# MCU.net
KiCad netlist of a schematic drawn in Altium Designer
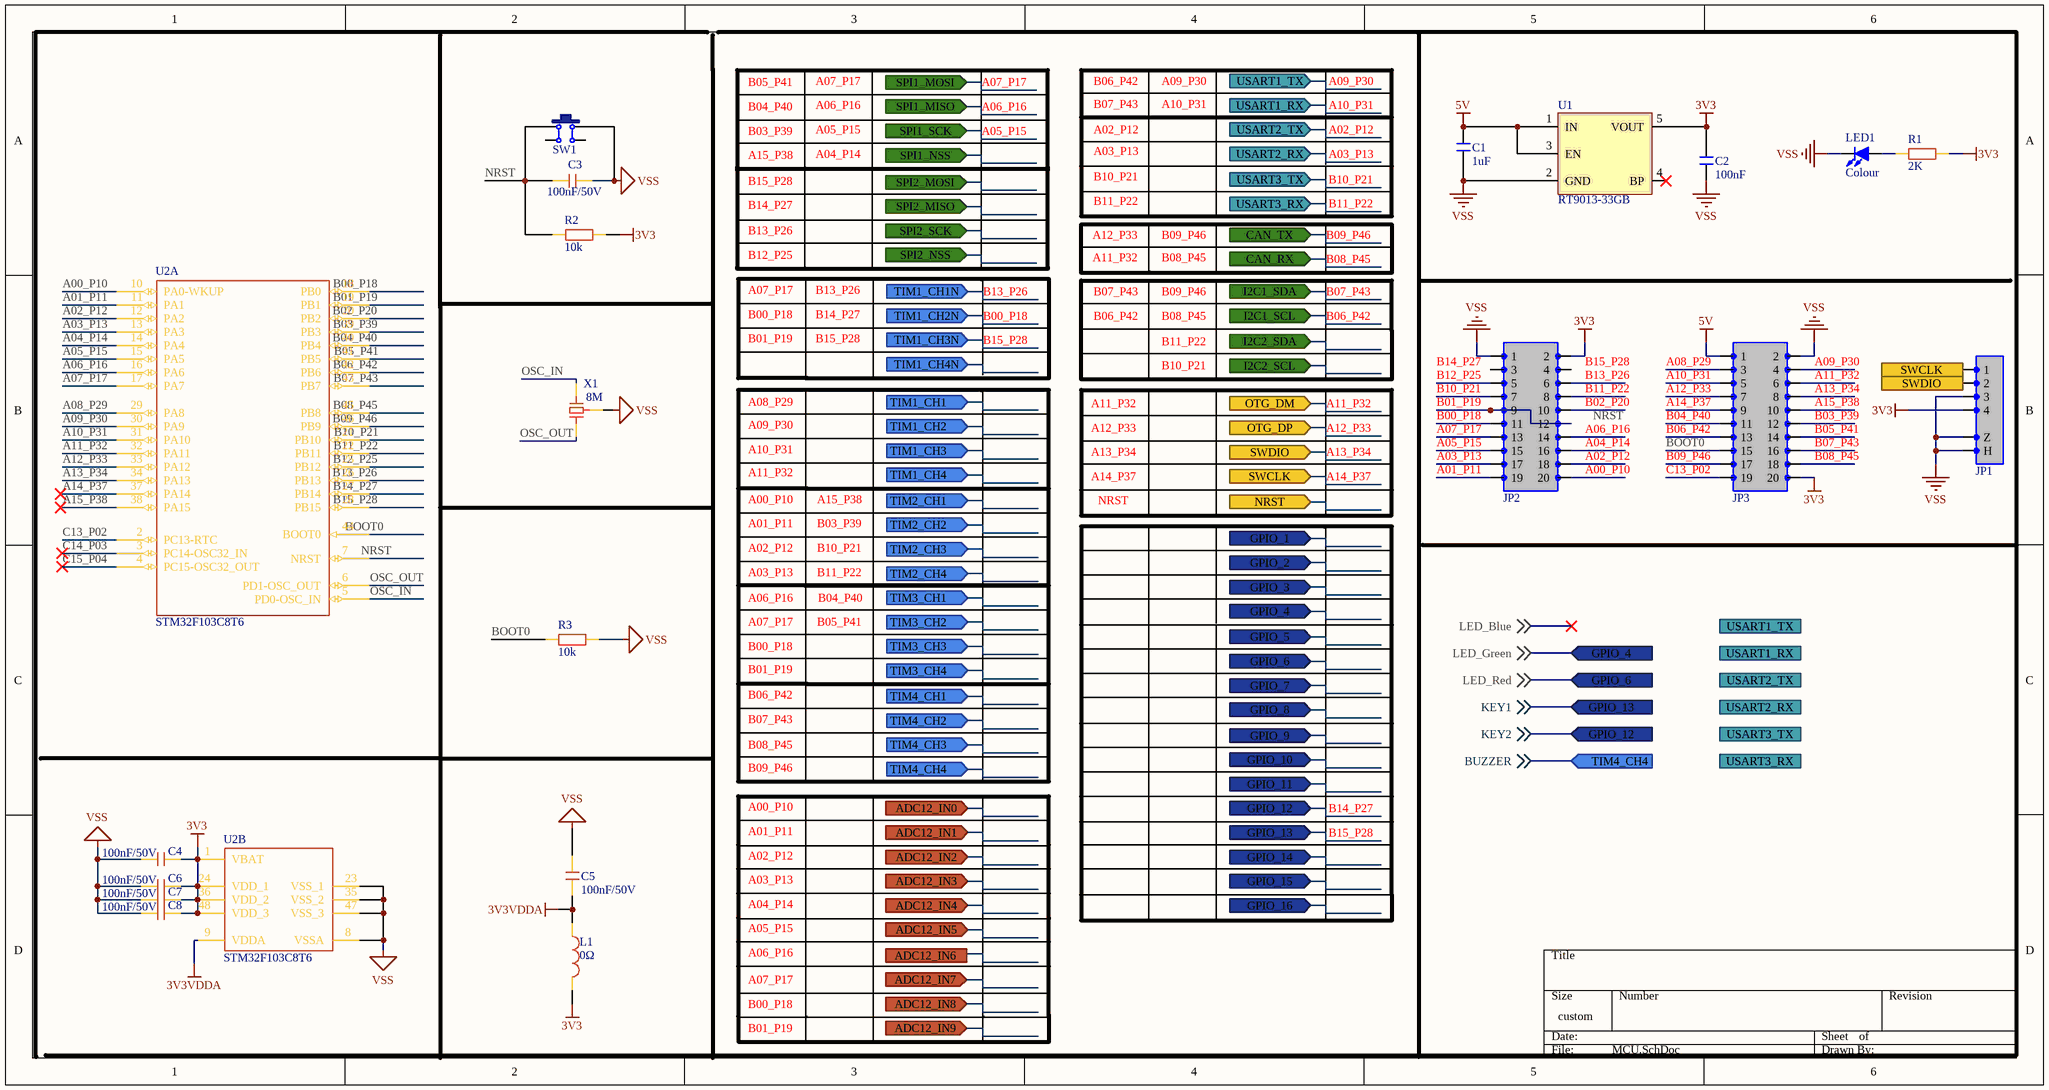
[diagram p0: MCU.SchDoc]

(export (version "E")
  (design (tool "Eeschema 10.0.6"))
  (components
    (comp (ref "C1")
      (value "1uF")
      (footprint "C 0603_L")
      (description "无极性贴片电容")
      (fields (field (name "版权归属") "源创客"))
      (libsource (lib "3.2-电容") (part "C"))
    )
    (comp (ref "C2")
      (value "100nF")
      (footprint "C 0603_L")
      (description "无极性贴片电容")
      (fields (field (name "版权归属") "源创客"))
      (libsource (lib "3.2-电容") (part "C"))
    )
    (comp (ref "C3")
      (value "100nF/50V")
      (footprint "C 0603_L")
      (description "贴片电容")
      (libsource (lib "Propitious Clouds_SCHLIB") (part "无极贴片电容"))
    )
    (comp (ref "C4")
      (value "100nF/50V")
      (footprint "C 0603_L")
      (description "贴片电容")
      (libsource (lib "Propitious Clouds_SCHLIB") (part "无极贴片电容"))
    )
    (comp (ref "C5")
      (value "100nF/50V")
      (footprint "C 0603_L")
      (description "贴片电容")
      (libsource (lib "Propitious Clouds_SCHLIB") (part "无极贴片电容"))
    )
    (comp (ref "C6")
      (value "100nF/50V")
      (footprint "C 0603_L")
      (description "贴片电容")
      (libsource (lib "Propitious Clouds_SCHLIB") (part "无极贴片电容"))
    )
    (comp (ref "C7")
      (value "100nF/50V")
      (footprint "C 0603_L")
      (description "贴片电容")
      (libsource (lib "Propitious Clouds_SCHLIB") (part "无极贴片电容"))
    )
    (comp (ref "C8")
      (value "100nF/50V")
      (footprint "C 0603_L")
      (description "贴片电容")
      (libsource (lib "Propitious Clouds_SCHLIB") (part "无极贴片电容"))
    )
    (comp (ref "JP1")
      (value "HDR-1X4")
      (footprint "GH 1.25-WS-4P")
      (description "4P接插件")
      (fields (field (name "版权归属") "源创客"))
      (libsource (lib "14.3-接插件-脚距1.25") (part "Header 4"))
    )
    (comp (ref "JP2")
      (value "Header 2X10")
      (footprint "HDR2.54-LI-2x10P")
      (description "10*2P接插件")
      (fields (field (name "版权归属") "源创客"))
      (libsource (lib "14.6-接插件-脚距2.54") (part "Header 10X2"))
    )
    (comp (ref "JP3")
      (value "Header 2X10")
      (footprint "HDR2.54-LI-2x10P")
      (description "10*2P接插件")
      (fields (field (name "版权归属") "源创客"))
      (libsource (lib "14.6-接插件-脚距2.54") (part "Header 10X2"))
    )
    (comp (ref "L1")
      (value "0Ω")
      (footprint "L 0603")
      (description "小功率贴片电感")
      (libsource (lib "Propitious Clouds_SCHLIB") (part "磁珠"))
    )
    (comp (ref "LED1")
      (value "Colour")
      (footprint "LED 0603R")
      (description "贴片LED")
      (fields (field (name "版权归属") "源创客"))
      (libsource (lib "7.1-LED") (part "LED-SMD"))
    )
    (comp (ref "R1")
      (value "2K")
      (footprint "R 0603_L")
      (description "贴片电阻1%精度")
      (libsource (lib "Propitious Clouds_SCHLIB") (part "电阻"))
    )
    (comp (ref "R2")
      (value "10k")
      (footprint "R 0603_L")
      (description "贴片电阻1%精度")
      (libsource (lib "Propitious Clouds_SCHLIB") (part "电阻"))
    )
    (comp (ref "R3")
      (value "10k")
      (footprint "R 0603_L")
      (description "贴片电阻1%精度")
      (libsource (lib "Propitious Clouds_SCHLIB") (part "电阻"))
    )
    (comp (ref "SW1")
      (value "3.2x4.2x2.5")
      (footprint "TSW SMD-3*4*2")
      (description "3.2x4.2轻触开关")
      (fields (field (name "版权归属") "源创客"))
      (libsource (lib "6.1-按键") (part "TSW SMD-3x4_D"))
    )
    (comp (ref "U1")
      (value "RT9013-33GB")
      (footprint "SOT23-5")
      (libsource (lib "Schlib1") (part "RT9193-33GB"))
    )
    (comp (ref "U2")
      (value "STM32F103C8T6")
      (footprint "LQFP48 7X7_L")
      (description "STM32F103C8T6是一款由意法半导体公司（ST）推出的基于Cortex-M3内核的32位微控制器，硬件采用LQFP48封装，属于ST公司微控制器中的STM32系列。")
      (libsource (lib "Propitious Clouds_SCHLIB") (part "STM32F103C8T6"))
    )
    (comp (ref "X1")
      (value "8M")
      (footprint "OSC 3213-3P")
      (description "3脚内置电容无源晶振")
      (libsource (lib "Propitious Clouds_SCHLIB") (part "XTAL-3P"))
    )
  )
  (nets
    (net (code "1") (name "/A00_P10") (class "Default")
      (node (ref "JP2") (pin "20") (pinfunction "20_20") (pintype "passive"))
      (node (ref "U2") (pin "10") (pinfunction "PA0-WKUP_10") (pintype "bidirectional"))
    )
    (net (code "2") (name "/A01_P11") (class "Default")
      (node (ref "JP2") (pin "19") (pinfunction "19_19") (pintype "passive"))
      (node (ref "U2") (pin "11") (pinfunction "PA1_11") (pintype "bidirectional"))
    )
    (net (code "3") (name "/A02_P12") (class "Default")
      (node (ref "JP2") (pin "18") (pinfunction "18_18") (pintype "passive"))
      (node (ref "U2") (pin "12") (pinfunction "PA2_12") (pintype "bidirectional"))
    )
    (net (code "4") (name "/A03_P13") (class "Default")
      (node (ref "JP2") (pin "17") (pinfunction "17_17") (pintype "passive"))
      (node (ref "U2") (pin "13") (pinfunction "PA3_13") (pintype "bidirectional"))
    )
    (net (code "5") (name "/A04_P14") (class "Default")
      (node (ref "JP2") (pin "16") (pinfunction "16_16") (pintype "passive"))
      (node (ref "U2") (pin "14") (pinfunction "PA4_14") (pintype "bidirectional"))
    )
    (net (code "6") (name "/A05_P15") (class "Default")
      (node (ref "JP2") (pin "15") (pinfunction "15_15") (pintype "passive"))
      (node (ref "U2") (pin "15") (pinfunction "PA5_15") (pintype "bidirectional"))
    )
    (net (code "7") (name "/A06_P16") (class "Default")
      (node (ref "JP2") (pin "14") (pinfunction "14_14") (pintype "passive"))
      (node (ref "U2") (pin "16") (pinfunction "PA6_16") (pintype "bidirectional"))
    )
    (net (code "8") (name "/A07_P17") (class "Default")
      (node (ref "JP2") (pin "13") (pinfunction "13_13") (pintype "passive"))
      (node (ref "U2") (pin "17") (pinfunction "PA7_17") (pintype "bidirectional"))
    )
    (net (code "9") (name "/A08_P29") (class "Default")
      (node (ref "JP3") (pin "3") (pinfunction "3_3") (pintype "passive"))
      (node (ref "U2") (pin "29") (pinfunction "PA8_29") (pintype "bidirectional"))
    )
    (net (code "10") (name "/A09_P30") (class "Default")
      (node (ref "JP3") (pin "4") (pinfunction "4_4") (pintype "passive"))
      (node (ref "U2") (pin "30") (pinfunction "PA9_30") (pintype "bidirectional"))
    )
    (net (code "11") (name "/A10_P31") (class "Default")
      (node (ref "JP3") (pin "5") (pinfunction "5_5") (pintype "passive"))
      (node (ref "U2") (pin "31") (pinfunction "PA10_31") (pintype "bidirectional"))
    )
    (net (code "12") (name "/A11_P32") (class "Default")
      (node (ref "JP3") (pin "6") (pinfunction "6_6") (pintype "passive"))
      (node (ref "U2") (pin "32") (pinfunction "PA11_32") (pintype "bidirectional"))
    )
    (net (code "13") (name "/A12_P33") (class "Default")
      (node (ref "JP3") (pin "7") (pinfunction "7_7") (pintype "passive"))
      (node (ref "U2") (pin "33") (pinfunction "PA12_33") (pintype "bidirectional"))
    )
    (net (code "14") (name "/A13_P34") (class "Default")
      (node (ref "JP1") (pin "2") (pinfunction "2_2") (pintype "passive"))
      (node (ref "JP3") (pin "8") (pinfunction "8_8") (pintype "passive"))
      (node (ref "U2") (pin "34") (pinfunction "PA13_34") (pintype "bidirectional"))
    )
    (net (code "15") (name "/A14_P37") (class "Default")
      (node (ref "JP1") (pin "1") (pinfunction "1_1") (pintype "passive"))
      (node (ref "JP3") (pin "9") (pinfunction "9_9") (pintype "passive"))
      (node (ref "U2") (pin "37") (pinfunction "PA14_37") (pintype "bidirectional"))
    )
    (net (code "16") (name "/A15_P38") (class "Default")
      (node (ref "JP3") (pin "10") (pinfunction "10_10") (pintype "passive"))
      (node (ref "U2") (pin "38") (pinfunction "PA15_38") (pintype "bidirectional"))
    )
    (net (code "27") (name "/B00_P18") (class "Default")
      (node (ref "JP2") (pin "11") (pinfunction "11_11") (pintype "passive"))
      (node (ref "U2") (pin "18") (pinfunction "PB0_18") (pintype "bidirectional"))
    )
    (net (code "28") (name "/B01_P19") (class "Default")
      (node (ref "JP2") (pin "12") (pinfunction "12_12") (pintype "passive"))
      (node (ref "JP2") (pin "9") (pinfunction "9_9") (pintype "passive"))
      (node (ref "U2") (pin "19") (pinfunction "PB1_19") (pintype "bidirectional"))
    )
    (net (code "29") (name "/B02_P20") (class "Default")
      (node (ref "JP2") (pin "10") (pinfunction "10_10") (pintype "passive"))
      (node (ref "U2") (pin "20") (pinfunction "PB2_20") (pintype "bidirectional"))
    )
    (net (code "30") (name "/B03_P39") (class "Default")
      (node (ref "JP3") (pin "12") (pinfunction "12_12") (pintype "passive"))
      (node (ref "U2") (pin "39") (pinfunction "PB3_39") (pintype "bidirectional"))
    )
    (net (code "31") (name "/B04_P40") (class "Default")
      (node (ref "JP3") (pin "11") (pinfunction "11_11") (pintype "passive"))
      (node (ref "U2") (pin "40") (pinfunction "PB4_40") (pintype "bidirectional"))
    )
    (net (code "32") (name "/B05_P41") (class "Default")
      (node (ref "JP3") (pin "14") (pinfunction "14_14") (pintype "passive"))
      (node (ref "U2") (pin "41") (pinfunction "PB5_41") (pintype "bidirectional"))
    )
    (net (code "33") (name "/B06_P42") (class "Default")
      (node (ref "JP3") (pin "13") (pinfunction "13_13") (pintype "passive"))
      (node (ref "U2") (pin "42") (pinfunction "PB6_42") (pintype "bidirectional"))
    )
    (net (code "34") (name "/B07_P43") (class "Default")
      (node (ref "JP3") (pin "16") (pinfunction "16_16") (pintype "passive"))
      (node (ref "U2") (pin "43") (pinfunction "PB7_43") (pintype "bidirectional"))
    )
    (net (code "35") (name "/B08_P45") (class "Default")
      (node (ref "JP3") (pin "18") (pinfunction "18_18") (pintype "passive"))
      (node (ref "U2") (pin "45") (pinfunction "PB8_45") (pintype "bidirectional"))
    )
    (net (code "36") (name "/B09_P46") (class "Default")
      (node (ref "JP3") (pin "17") (pinfunction "17_17") (pintype "passive"))
      (node (ref "U2") (pin "46") (pinfunction "PB9_46") (pintype "bidirectional"))
    )
    (net (code "37") (name "/B10_P21") (class "Default")
      (node (ref "JP2") (pin "7") (pinfunction "7_7") (pintype "passive"))
      (node (ref "U2") (pin "21") (pinfunction "PB10_21") (pintype "bidirectional"))
    )
    (net (code "38") (name "/B11_P22") (class "Default")
      (node (ref "JP2") (pin "8") (pinfunction "8_8") (pintype "passive"))
      (node (ref "U2") (pin "22") (pinfunction "PB11_22") (pintype "bidirectional"))
    )
    (net (code "39") (name "/B12_P25") (class "Default")
      (node (ref "JP2") (pin "5") (pinfunction "5_5") (pintype "passive"))
      (node (ref "U2") (pin "25") (pinfunction "PB12_25") (pintype "bidirectional"))
    )
    (net (code "40") (name "/B13_P26") (class "Default")
      (node (ref "JP2") (pin "6") (pinfunction "6_6") (pintype "passive"))
      (node (ref "U2") (pin "26") (pinfunction "PB13_26") (pintype "bidirectional"))
    )
    (net (code "41") (name "/BOOT0") (class "Default")
      (node (ref "JP3") (pin "15") (pinfunction "15_15") (pintype "passive"))
      (node (ref "R3") (pin "1") (pinfunction "1_1") (pintype "passive"))
      (node (ref "U2") (pin "44") (pinfunction "BOOT0_44") (pintype "input"))
    )
    (net (code "42") (name "/C13_P02") (class "Default")
      (node (ref "JP3") (pin "19") (pinfunction "19_19") (pintype "passive"))
      (node (ref "U2") (pin "2") (pinfunction "PC13-RTC_2") (pintype "bidirectional"))
    )
    (net (code "43") (name "/C14_P03") (class "Default")
      (node (ref "U2") (pin "3") (pinfunction "PC14-OSC32_IN_3") (pintype "bidirectional+no_connect"))
    )
    (net (code "44") (name "/C15_P04") (class "Default")
      (node (ref "U2") (pin "4") (pinfunction "PC15-OSC32_OUT_4") (pintype "bidirectional+no_connect"))
    )
    (net (code "59") (name "/NRST") (class "Default")
      (node (ref "C3") (pin "1") (pinfunction "1_1") (pintype "passive"))
      (node (ref "R2") (pin "1") (pinfunction "1_1") (pintype "passive"))
      (node (ref "SW1") (pin "2") (pinfunction "2_2") (pintype "passive"))
      (node (ref "U2") (pin "7") (pinfunction "NRST_7") (pintype "bidirectional"))
    )
    (net (code "60") (name "/OSC_IN") (class "Default")
      (node (ref "U2") (pin "5") (pinfunction "PD0-OSC_IN_5") (pintype "bidirectional"))
      (node (ref "X1") (pin "2") (pinfunction "2_2") (pintype "passive"))
    )
    (net (code "61") (name "/OSC_OUT") (class "Default")
      (node (ref "U2") (pin "6") (pinfunction "PD1-OSC_OUT_6") (pintype "bidirectional"))
      (node (ref "X1") (pin "1") (pinfunction "1_1") (pintype "passive"))
    )
    (net (code "83") (name "3V3") (class "Default")
      (node (ref "C2") (pin "1") (pinfunction "1_1") (pintype "passive"))
      (node (ref "C4") (pin "2") (pinfunction "2_2") (pintype "passive"))
      (node (ref "C6") (pin "2") (pinfunction "2_2") (pintype "passive"))
      (node (ref "C7") (pin "2") (pinfunction "2_2") (pintype "passive"))
      (node (ref "C8") (pin "2") (pinfunction "2_2") (pintype "passive"))
      (node (ref "JP1") (pin "4") (pinfunction "4_4") (pintype "passive"))
      (node (ref "JP2") (pin "2") (pinfunction "2_2") (pintype "passive"))
      (node (ref "JP3") (pin "20") (pinfunction "20_20") (pintype "passive"))
      (node (ref "L1") (pin "2") (pinfunction "2_2") (pintype "passive"))
      (node (ref "R1") (pin "1") (pinfunction "1_1") (pintype "passive"))
      (node (ref "R2") (pin "2") (pinfunction "2_2") (pintype "passive"))
      (node (ref "U1") (pin "5") (pinfunction "VOUT_5") (pintype "passive"))
      (node (ref "U2") (pin "1") (pinfunction "VBAT_1") (pintype "power_in"))
      (node (ref "U2") (pin "24") (pinfunction "VDD_1_24") (pintype "power_in"))
      (node (ref "U2") (pin "36") (pinfunction "VDD_2_36") (pintype "power_in"))
      (node (ref "U2") (pin "48") (pinfunction "VDD_3_48") (pintype "power_in"))
    )
    (net (code "84") (name "3V3VDDA") (class "Default")
      (node (ref "C5") (pin "2") (pinfunction "2_2") (pintype "passive"))
      (node (ref "L1") (pin "1") (pinfunction "1_1") (pintype "passive"))
      (node (ref "U2") (pin "9") (pinfunction "VDDA_9") (pintype "power_in"))
    )
    (net (code "85") (name "5V") (class "Default")
      (node (ref "C1") (pin "1") (pinfunction "1_1") (pintype "passive"))
      (node (ref "JP3") (pin "1") (pinfunction "1_1") (pintype "passive"))
      (node (ref "U1") (pin "1") (pinfunction "IN_1") (pintype "passive"))
      (node (ref "U1") (pin "3") (pinfunction "EN_3") (pintype "passive"))
    )
    (net (code "87") (name "KEY1") (class "Default")
      (node (ref "U2") (pin "28") (pinfunction "PB15_28") (pintype "bidirectional"))
    )
    (net (code "88") (name "KEY2") (class "Default")
      (node (ref "U2") (pin "27") (pinfunction "PB14_27") (pintype "bidirectional"))
    )
    (net (code "92") (name "Net-(LED1-A)") (class "Default")
      (node (ref "LED1") (pin "1") (pinfunction "A_1") (pintype "passive"))
      (node (ref "R1") (pin "2") (pinfunction "2_2") (pintype "passive"))
    )
    (net (code "93") (name "VSS") (class "Default")
      (node (ref "C1") (pin "2") (pinfunction "2_2") (pintype "passive"))
      (node (ref "C2") (pin "2") (pinfunction "2_2") (pintype "passive"))
      (node (ref "C3") (pin "2") (pinfunction "2_2") (pintype "passive"))
      (node (ref "C4") (pin "1") (pinfunction "1_1") (pintype "passive"))
      (node (ref "C5") (pin "1") (pinfunction "1_1") (pintype "passive"))
      (node (ref "C6") (pin "1") (pinfunction "1_1") (pintype "passive"))
      (node (ref "C7") (pin "1") (pinfunction "1_1") (pintype "passive"))
      (node (ref "C8") (pin "1") (pinfunction "1_1") (pintype "passive"))
      (node (ref "JP1") (pin "0") (pinfunction "Z_0") (pintype "passive"))
      (node (ref "JP1") (pin "100") (pinfunction "H_100") (pintype "passive"))
      (node (ref "JP1") (pin "3") (pinfunction "3_3") (pintype "passive"))
      (node (ref "JP2") (pin "1") (pinfunction "1_1") (pintype "passive"))
      (node (ref "JP3") (pin "2") (pinfunction "2_2") (pintype "passive"))
      (node (ref "LED1") (pin "2") (pinfunction "K_2") (pintype "passive"))
      (node (ref "R3") (pin "2") (pinfunction "2_2") (pintype "passive"))
      (node (ref "SW1") (pin "1") (pinfunction "1_1") (pintype "passive"))
      (node (ref "U1") (pin "2") (pinfunction "GND_2") (pintype "passive"))
      (node (ref "U2") (pin "23") (pinfunction "VSS_1_23") (pintype "power_in"))
      (node (ref "U2") (pin "35") (pinfunction "VSS_2_35") (pintype "power_in"))
      (node (ref "U2") (pin "47") (pinfunction "VSS_3_47") (pintype "power_in"))
      (node (ref "U2") (pin "8") (pinfunction "VSSA_8") (pintype "power_in"))
      (node (ref "X1") (pin "3") (pinfunction "3_3") (pintype "passive"))
    )
    (net (code "94") (name "unconnected-(JP2-Pad3)") (class "Default")
      (node (ref "JP2") (pin "3") (pinfunction "3_3") (pintype "passive"))
    )
    (net (code "95") (name "unconnected-(JP2-Pad4)") (class "Default")
      (node (ref "JP2") (pin "4") (pinfunction "4_4") (pintype "passive"))
    )
    (net (code "96") (name "unconnected-(SW1-Pad3)") (class "Default")
      (node (ref "SW1") (pin "3") (pinfunction "3_3") (pintype "passive"))
    )
    (net (code "97") (name "unconnected-(SW1-Pad4)") (class "Default")
      (node (ref "SW1") (pin "4") (pinfunction "4_4") (pintype "passive"))
    )
    (net (code "98") (name "unconnected-(U1-BP-Pad4)") (class "Default")
      (node (ref "U1") (pin "4") (pinfunction "BP_4") (pintype "passive+no_connect"))
    )
  )
)
